# LED_driverV1_1.net
KiCad netlist of a schematic drawn in EAGLE
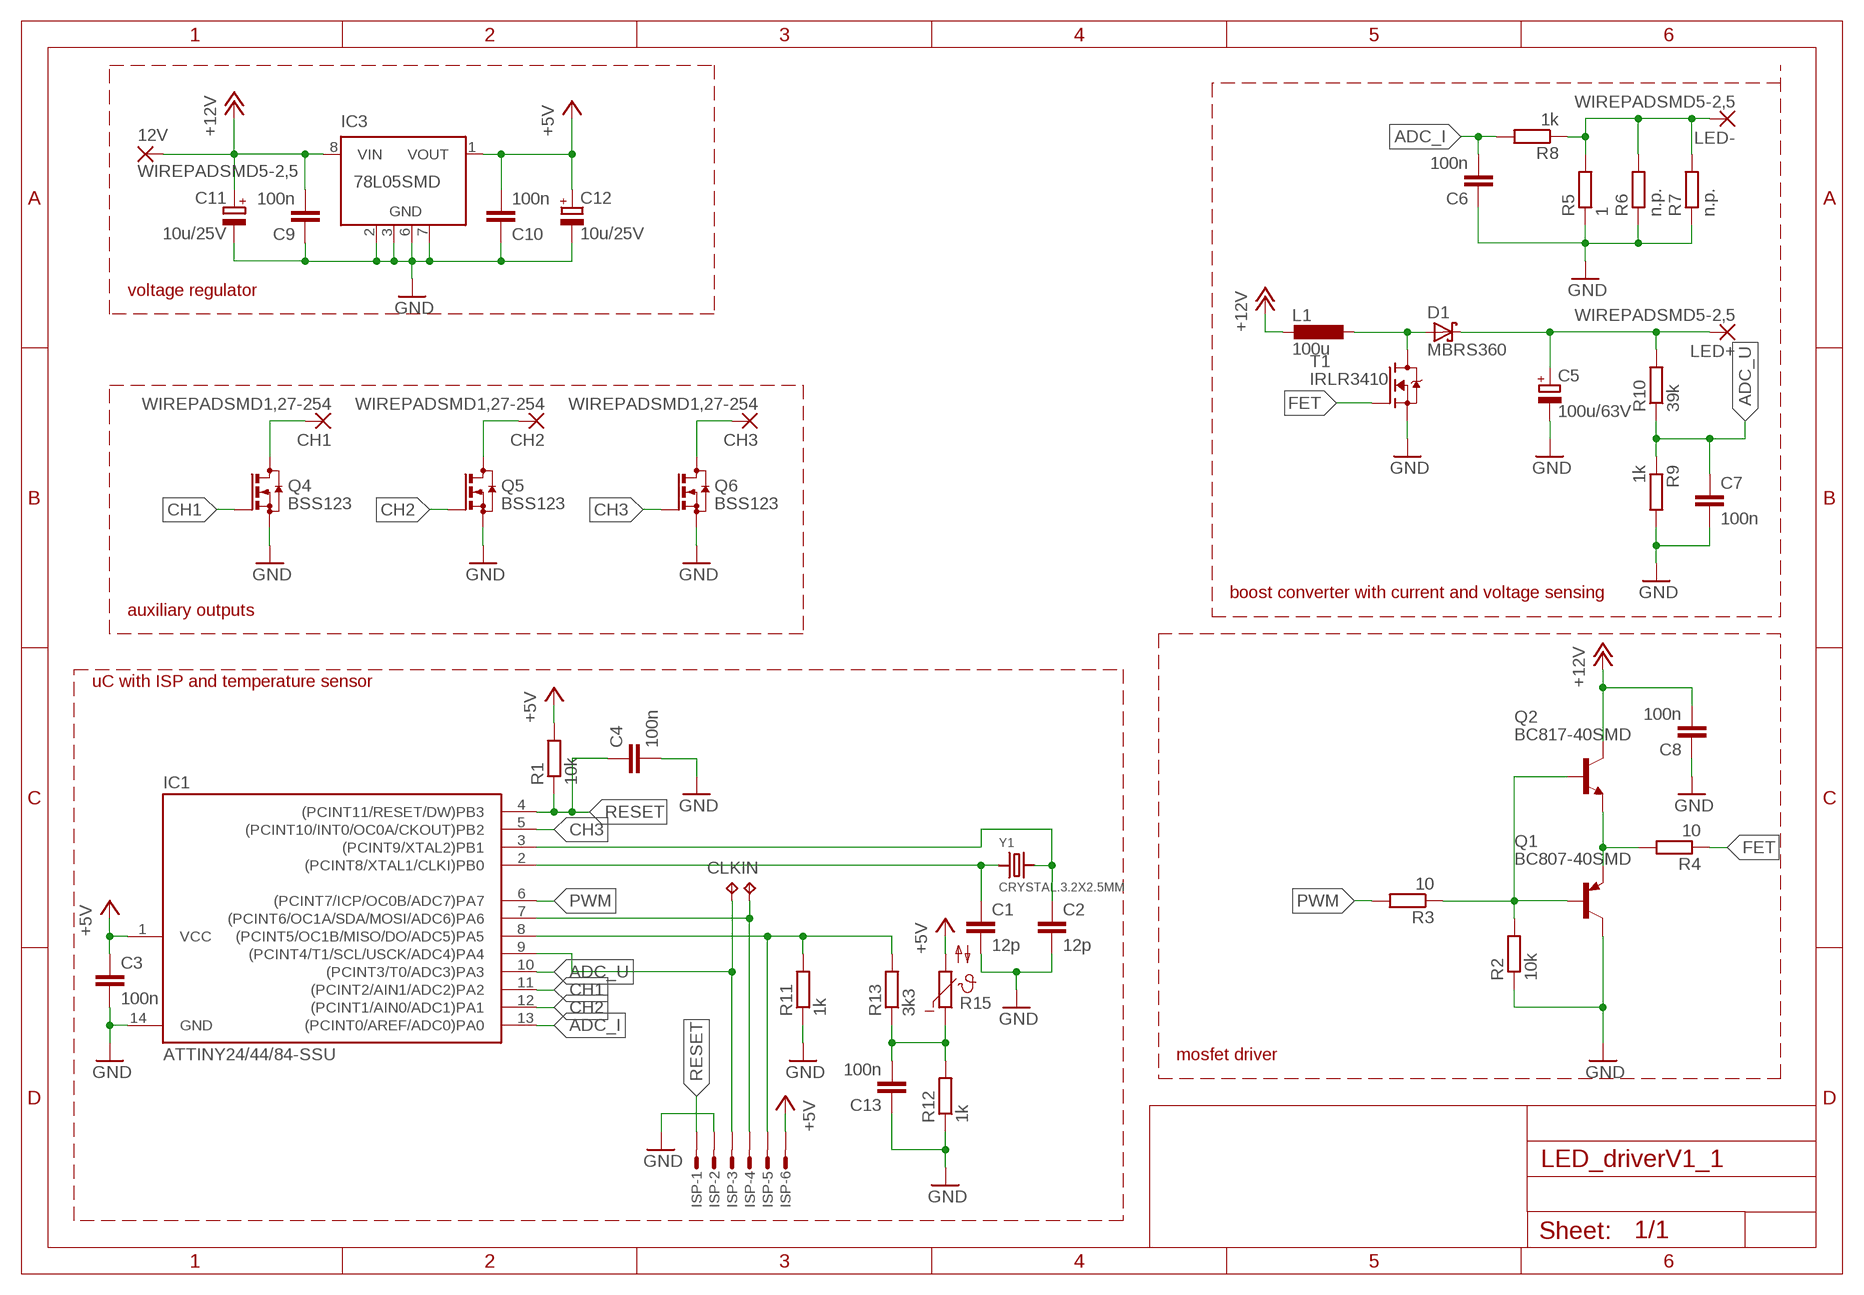
[diagram p0: schematic, sheet 1]

(export (version "E")
  (design (tool "Eeschema 10.0.6"))
  (components
    (comp (ref "12V")
      (value "WIREPADSMD5-2,5")
      (footprint "eagle-import:5-2,5")
      (libsource (lib "eagle-import") (part "WIREPADSMD5-2,5"))
    )
    (comp (ref "C1")
      (value "12p")
      (footprint "eagle-import:C0603K")
      (libsource (lib "eagle-import") (part "C-EUC0603K"))
    )
    (comp (ref "C2")
      (value "12p")
      (footprint "eagle-import:C0603K")
      (libsource (lib "eagle-import") (part "C-EUC0603K"))
    )
    (comp (ref "C3")
      (value "100n")
      (footprint "eagle-import:C0603K")
      (libsource (lib "eagle-import") (part "C-EUC0603K"))
    )
    (comp (ref "C4")
      (value "100n")
      (footprint "eagle-import:C0603K")
      (libsource (lib "eagle-import") (part "C-EUC0603K"))
    )
    (comp (ref "C5")
      (value "100u/63V")
      (footprint "eagle-import:153CLV-1010")
      (libsource (lib "eagle-import") (part "CPOL-EU153CLV-1010"))
    )
    (comp (ref "C6")
      (value "100n")
      (footprint "eagle-import:C0603K")
      (libsource (lib "eagle-import") (part "C-EUC0603K"))
    )
    (comp (ref "C7")
      (value "100n")
      (footprint "eagle-import:C0603K")
      (libsource (lib "eagle-import") (part "C-EUC0603K"))
    )
    (comp (ref "C8")
      (value "100n")
      (footprint "eagle-import:C0603K")
      (libsource (lib "eagle-import") (part "C-EUC0603K"))
    )
    (comp (ref "C9")
      (value "100n")
      (footprint "eagle-import:C0603K")
      (libsource (lib "eagle-import") (part "C-EUC0603K"))
    )
    (comp (ref "C10")
      (value "100n")
      (footprint "eagle-import:C0603K")
      (libsource (lib "eagle-import") (part "C-EUC0603K"))
    )
    (comp (ref "C11")
      (value "10u/25V")
      (footprint "eagle-import:153CLV-0405")
      (libsource (lib "eagle-import") (part "CPOL-EU153CLV-0405"))
    )
    (comp (ref "C12")
      (value "10u/25V")
      (footprint "eagle-import:153CLV-0405")
      (libsource (lib "eagle-import") (part "CPOL-EU153CLV-0405"))
    )
    (comp (ref "C13")
      (value "100n")
      (footprint "eagle-import:C0603K")
      (libsource (lib "eagle-import") (part "C-EUC0603K"))
    )
    (comp (ref "CH1")
      (value "WIREPADSMD1,27-254")
      (footprint "eagle-import:SMD1,27-2,54")
      (libsource (lib "eagle-import") (part "WIREPADSMD1,27-254"))
    )
    (comp (ref "CH2")
      (value "WIREPADSMD1,27-254")
      (footprint "eagle-import:SMD1,27-2,54")
      (libsource (lib "eagle-import") (part "WIREPADSMD1,27-254"))
    )
    (comp (ref "CH3")
      (value "WIREPADSMD1,27-254")
      (footprint "eagle-import:SMD1,27-2,54")
      (libsource (lib "eagle-import") (part "WIREPADSMD1,27-254"))
    )
    (comp (ref "CLK")
      (value "TPTP15R")
      (footprint "eagle-import:TP15R")
      (libsource (lib "eagle-import") (part "TPTP15R"))
    )
    (comp (ref "D1")
      (value "MBRS360")
      (footprint "eagle-import:SMC")
      (libsource (lib "eagle-import") (part "SCHOTTKY-DIODESMC"))
    )
    (comp (ref "IC1")
      (value "ATTINY24/44/84-SSU")
      (footprint "eagle-import:SOIC14")
      (libsource (lib "eagle-import") (part "ATTINY24/44/84-SSU"))
    )
    (comp (ref "IC3")
      (value "78L05SMD")
      (footprint "eagle-import:SO08")
      (libsource (lib "eagle-import") (part "78LSMD05"))
    )
    (comp (ref "IN")
      (value "TPTP15R")
      (footprint "eagle-import:TP15R")
      (libsource (lib "eagle-import") (part "TPTP15R"))
    )
    (comp (ref "ISP")
      (value "MICROMATCH-6SMF")
      (footprint "eagle-import:MMT-F-SMD-6")
      (libsource (lib "eagle-import") (part "MICROMATCH-6SMF"))
    )
    (comp (ref "L1")
      (value "100u")
      (footprint "eagle-import:PISM")
      (libsource (lib "eagle-import") (part "L-EUPISM"))
    )
    (comp (ref "LED+")
      (value "WIREPADSMD5-2,5")
      (footprint "eagle-import:5-2,5")
      (libsource (lib "eagle-import") (part "WIREPADSMD5-2,5"))
    )
    (comp (ref "LED-")
      (value "WIREPADSMD5-2,5")
      (footprint "eagle-import:5-2,5")
      (libsource (lib "eagle-import") (part "WIREPADSMD5-2,5"))
    )
    (comp (ref "Q1")
      (value "BC807-40SMD")
      (footprint "eagle-import:SOT23-BEC")
      (libsource (lib "eagle-import") (part "BC807SMD-40"))
    )
    (comp (ref "Q2")
      (value "BC817-40SMD")
      (footprint "eagle-import:SOT23-BEC")
      (libsource (lib "eagle-import") (part "BC817SMD-40"))
    )
    (comp (ref "Q4")
      (value "BSS123")
      (footprint "eagle-import:SOT23")
      (libsource (lib "eagle-import") (part "BSS123"))
    )
    (comp (ref "Q5")
      (value "BSS123")
      (footprint "eagle-import:SOT23")
      (libsource (lib "eagle-import") (part "BSS123"))
    )
    (comp (ref "Q6")
      (value "BSS123")
      (footprint "eagle-import:SOT23")
      (libsource (lib "eagle-import") (part "BSS123"))
    )
    (comp (ref "R1")
      (value "10k")
      (footprint "eagle-import:R0603")
      (libsource (lib "eagle-import") (part "R-EU_R0603"))
    )
    (comp (ref "R2")
      (value "10k")
      (footprint "eagle-import:R0603")
      (libsource (lib "eagle-import") (part "R-EU_R0603"))
    )
    (comp (ref "R3")
      (value "10")
      (footprint "eagle-import:R0603")
      (libsource (lib "eagle-import") (part "R-EU_R0603"))
    )
    (comp (ref "R4")
      (value "10")
      (footprint "eagle-import:R0603")
      (libsource (lib "eagle-import") (part "R-EU_R0603"))
    )
    (comp (ref "R5")
      (value "1")
      (footprint "eagle-import:R1206")
      (libsource (lib "eagle-import") (part "resistor_R-EU_R1206"))
    )
    (comp (ref "R6")
      (value "n.p.")
      (footprint "eagle-import:R1206")
      (libsource (lib "eagle-import") (part "resistor_R-EU_R1206"))
    )
    (comp (ref "R7")
      (value "n.p.")
      (footprint "eagle-import:R1206")
      (libsource (lib "eagle-import") (part "resistor_R-EU_R1206"))
    )
    (comp (ref "R8")
      (value "1k")
      (footprint "eagle-import:R0603")
      (libsource (lib "eagle-import") (part "R-EU_R0603"))
    )
    (comp (ref "R9")
      (value "1k")
      (footprint "eagle-import:R0603")
      (libsource (lib "eagle-import") (part "R-EU_R0603"))
    )
    (comp (ref "R10")
      (value "39k")
      (footprint "eagle-import:R0603")
      (libsource (lib "eagle-import") (part "R-EU_R0603"))
    )
    (comp (ref "R11")
      (value "1k")
      (footprint "eagle-import:R0603")
      (libsource (lib "eagle-import") (part "R-EU_R0603"))
    )
    (comp (ref "R12")
      (value "1k")
      (footprint "eagle-import:R0603")
      (libsource (lib "eagle-import") (part "R-EU_R0603"))
    )
    (comp (ref "R13")
      (value "3k3")
      (footprint "eagle-import:R0603")
      (libsource (lib "eagle-import") (part "R-EU_R0603"))
    )
    (comp (ref "R15")
      (value "NTC640")
      (footprint "eagle-import:P640")
      (libsource (lib "eagle-import") (part "NTC640"))
    )
    (comp (ref "T1")
      (value "IRLR3410")
      (footprint "eagle-import:TO252")
      (libsource (lib "eagle-import") (part "IRLR3410"))
    )
    (comp (ref "Y1")
      (value "CRYSTAL.3.2X2.5MM")
      (footprint "eagle-import:3.2X2.5MM")
      (libsource (lib "eagle-import") (part "CRYSTAL.3.2X2.5MM"))
    )
  )
  (nets
    (net (code "1") (name "+5V") (class "Default")
      (node (ref "C10") (pin "2") (pinfunction "2_2") (pintype "passive"))
      (node (ref "C12") (pin "+") (pinfunction "+_+") (pintype "passive"))
      (node (ref "C3") (pin "1") (pinfunction "1_1") (pintype "passive"))
      (node (ref "IC1") (pin "1") (pinfunction "VCC_1") (pintype "power_in"))
      (node (ref "IC3") (pin "1") (pinfunction "VOUT_1") (pintype "output"))
      (node (ref "ISP") (pin "6") (pinfunction "S_6") (pintype "passive"))
      (node (ref "R1") (pin "2") (pinfunction "2_2") (pintype "passive"))
      (node (ref "R15") (pin "2") (pinfunction "2_2") (pintype "passive"))
    )
    (net (code "2") (name "+12V") (class "Default")
      (node (ref "12V") (pin "1") (pinfunction "P_1") (pintype "passive"))
      (node (ref "C11") (pin "+") (pinfunction "+_+") (pintype "passive"))
      (node (ref "C8") (pin "2") (pinfunction "2_2") (pintype "passive"))
      (node (ref "C9") (pin "2") (pinfunction "2_2") (pintype "passive"))
      (node (ref "IC3") (pin "8") (pinfunction "VIN_8") (pintype "passive"))
      (node (ref "L1") (pin "2") (pinfunction "2_2") (pintype "passive"))
      (node (ref "Q2") (pin "C") (pinfunction "C_C") (pintype "passive"))
    )
    (net (code "3") (name "ADC_I") (class "Default")
      (node (ref "C6") (pin "2") (pinfunction "2_2") (pintype "passive"))
      (node (ref "IC1") (pin "13") (pinfunction "(PCINT0/AREF/ADC0)PA0_13") (pintype "bidirectional"))
      (node (ref "R8") (pin "2") (pinfunction "2_2") (pintype "passive"))
    )
    (net (code "4") (name "ADC_U") (class "Default")
      (node (ref "C7") (pin "1") (pinfunction "1_1") (pintype "passive"))
      (node (ref "IC1") (pin "10") (pinfunction "(PCINT3/T0/ADC3)PA3_10") (pintype "bidirectional"))
      (node (ref "R10") (pin "1") (pinfunction "1_1") (pintype "passive"))
      (node (ref "R9") (pin "1") (pinfunction "1_1") (pintype "passive"))
    )
    (net (code "5") (name "CH1") (class "Default")
      (node (ref "IC1") (pin "11") (pinfunction "(PCINT2/AIN1/ADC2)PA2_11") (pintype "bidirectional"))
      (node (ref "Q4") (pin "1") (pinfunction "G_1") (pintype "passive"))
    )
    (net (code "6") (name "CH2") (class "Default")
      (node (ref "IC1") (pin "12") (pinfunction "(PCINT1/AIN0/ADC1)PA1_12") (pintype "bidirectional"))
      (node (ref "Q5") (pin "1") (pinfunction "G_1") (pintype "passive"))
    )
    (net (code "7") (name "CH3") (class "Default")
      (node (ref "IC1") (pin "5") (pinfunction "(PCINT10/INT0/OC0A/CKOUT)PB2_5") (pintype "bidirectional"))
      (node (ref "Q6") (pin "1") (pinfunction "G_1") (pintype "passive"))
    )
    (net (code "8") (name "FET") (class "Default")
      (node (ref "R4") (pin "1") (pinfunction "1_1") (pintype "passive"))
      (node (ref "T1") (pin "1") (pinfunction "G_1") (pintype "passive"))
    )
    (net (code "9") (name "GND") (class "Default")
      (node (ref "C1") (pin "2") (pinfunction "2_2") (pintype "passive"))
      (node (ref "C10") (pin "1") (pinfunction "1_1") (pintype "passive"))
      (node (ref "C11") (pin "-") (pinfunction "-_-") (pintype "passive"))
      (node (ref "C12") (pin "-") (pinfunction "-_-") (pintype "passive"))
      (node (ref "C13") (pin "1") (pinfunction "1_1") (pintype "passive"))
      (node (ref "C2") (pin "2") (pinfunction "2_2") (pintype "passive"))
      (node (ref "C3") (pin "2") (pinfunction "2_2") (pintype "passive"))
      (node (ref "C4") (pin "2") (pinfunction "2_2") (pintype "passive"))
      (node (ref "C5") (pin "-") (pinfunction "-_-") (pintype "passive"))
      (node (ref "C6") (pin "1") (pinfunction "1_1") (pintype "passive"))
      (node (ref "C7") (pin "2") (pinfunction "2_2") (pintype "passive"))
      (node (ref "C8") (pin "1") (pinfunction "1_1") (pintype "passive"))
      (node (ref "C9") (pin "1") (pinfunction "1_1") (pintype "passive"))
      (node (ref "IC1") (pin "14") (pinfunction "GND_14") (pintype "power_in"))
      (node (ref "IC3") (pin "2") (pinfunction "GND_2") (pintype "power_in"))
      (node (ref "IC3") (pin "3") (pinfunction "GND_3") (pintype "power_in"))
      (node (ref "IC3") (pin "6") (pinfunction "GND_6") (pintype "power_in"))
      (node (ref "IC3") (pin "7") (pinfunction "GND_7") (pintype "power_in"))
      (node (ref "ISP") (pin "2") (pinfunction "S_2") (pintype "passive"))
      (node (ref "Q1") (pin "C") (pinfunction "C_C") (pintype "passive"))
      (node (ref "Q4") (pin "2") (pinfunction "S_2") (pintype "passive"))
      (node (ref "Q5") (pin "2") (pinfunction "S_2") (pintype "passive"))
      (node (ref "Q6") (pin "2") (pinfunction "S_2") (pintype "passive"))
      (node (ref "R11") (pin "1") (pinfunction "1_1") (pintype "passive"))
      (node (ref "R12") (pin "1") (pinfunction "1_1") (pintype "passive"))
      (node (ref "R2") (pin "1") (pinfunction "1_1") (pintype "passive"))
      (node (ref "R5") (pin "1") (pinfunction "1_1") (pintype "passive"))
      (node (ref "R6") (pin "1") (pinfunction "1_1") (pintype "passive"))
      (node (ref "R7") (pin "1") (pinfunction "1_1") (pintype "passive"))
      (node (ref "R9") (pin "2") (pinfunction "2_2") (pintype "passive"))
      (node (ref "T1") (pin "2") (pinfunction "S_2") (pintype "passive"))
    )
    (net (code "10") (name "Net-(C13-Pad2)") (class "Default")
      (node (ref "C13") (pin "2") (pinfunction "2_2") (pintype "passive"))
      (node (ref "R12") (pin "2") (pinfunction "2_2") (pintype "passive"))
      (node (ref "R13") (pin "1") (pinfunction "1_1") (pintype "passive"))
      (node (ref "R15") (pin "1") (pinfunction "1_1") (pintype "passive"))
    )
    (net (code "11") (name "Net-(CH1-P)") (class "Default")
      (node (ref "CH1") (pin "1") (pinfunction "P_1") (pintype "passive"))
      (node (ref "Q4") (pin "3") (pinfunction "D_3") (pintype "passive"))
    )
    (net (code "12") (name "Net-(CH2-P)") (class "Default")
      (node (ref "CH2") (pin "1") (pinfunction "P_1") (pintype "passive"))
      (node (ref "Q5") (pin "3") (pinfunction "D_3") (pintype "passive"))
    )
    (net (code "13") (name "Net-(CH3-P)") (class "Default")
      (node (ref "CH3") (pin "1") (pinfunction "P_1") (pintype "passive"))
      (node (ref "Q6") (pin "3") (pinfunction "D_3") (pintype "passive"))
    )
    (net (code "14") (name "Net-(IC1-(PCINT4{slash}T1{slash}SCL{slash}USCK{slash}ADC4)PA4)") (class "Default")
      (node (ref "CLK") (pin "TP") (pinfunction "TP_TP") (pintype "input"))
      (node (ref "IC1") (pin "9") (pinfunction "(PCINT4/T1/SCL/USCK/ADC4)PA4_9") (pintype "bidirectional"))
      (node (ref "ISP") (pin "3") (pinfunction "S_3") (pintype "passive"))
    )
    (net (code "15") (name "Net-(IC1-(PCINT5{slash}OC1B{slash}MISO{slash}DO{slash}ADC5)PA5)") (class "Default")
      (node (ref "IC1") (pin "8") (pinfunction "(PCINT5/OC1B/MISO/DO/ADC5)PA5_8") (pintype "bidirectional"))
      (node (ref "ISP") (pin "5") (pinfunction "S_5") (pintype "passive"))
      (node (ref "R11") (pin "2") (pinfunction "2_2") (pintype "passive"))
      (node (ref "R13") (pin "2") (pinfunction "2_2") (pintype "passive"))
    )
    (net (code "16") (name "Net-(IC1-(PCINT6{slash}OC1A{slash}SDA{slash}MOSI{slash}ADC6)PA6)") (class "Default")
      (node (ref "IC1") (pin "7") (pinfunction "(PCINT6/OC1A/SDA/MOSI/ADC6)PA6_7") (pintype "bidirectional"))
      (node (ref "IN") (pin "TP") (pinfunction "TP_TP") (pintype "input"))
      (node (ref "ISP") (pin "4") (pinfunction "S_4") (pintype "passive"))
    )
    (net (code "17") (name "Net-(IC1-(PCINT8{slash}XTAL1{slash}CLKI)PB0)") (class "Default")
      (node (ref "C1") (pin "1") (pinfunction "1_1") (pintype "passive"))
      (node (ref "IC1") (pin "2") (pinfunction "(PCINT8/XTAL1/CLKI)PB0_2") (pintype "bidirectional"))
      (node (ref "Y1") (pin "1") (pinfunction "1_1") (pintype "passive"))
    )
    (net (code "18") (name "Net-(IC1-(PCINT9{slash}XTAL2)PB1)") (class "Default")
      (node (ref "C2") (pin "1") (pinfunction "1_1") (pintype "passive"))
      (node (ref "IC1") (pin "3") (pinfunction "(PCINT9/XTAL2)PB1_3") (pintype "bidirectional"))
      (node (ref "Y1") (pin "3") (pinfunction "2_3") (pintype "passive"))
    )
    (net (code "19") (name "Net-(LED+-P)") (class "Default")
      (node (ref "C5") (pin "+") (pinfunction "+_+") (pintype "passive"))
      (node (ref "D1") (pin "C") (pinfunction "C_C") (pintype "passive"))
      (node (ref "LED+") (pin "1") (pinfunction "P_1") (pintype "passive"))
      (node (ref "R10") (pin "2") (pinfunction "2_2") (pintype "passive"))
    )
    (net (code "20") (name "Net-(LED--P)") (class "Default")
      (node (ref "LED-") (pin "1") (pinfunction "P_1") (pintype "passive"))
      (node (ref "R5") (pin "2") (pinfunction "2_2") (pintype "passive"))
      (node (ref "R6") (pin "2") (pinfunction "2_2") (pintype "passive"))
      (node (ref "R7") (pin "2") (pinfunction "2_2") (pintype "passive"))
      (node (ref "R8") (pin "1") (pinfunction "1_1") (pintype "passive"))
    )
    (net (code "21") (name "Net-(Q1-PadB)") (class "Default")
      (node (ref "Q1") (pin "B") (pinfunction "B_B") (pintype "passive"))
      (node (ref "Q2") (pin "B") (pinfunction "B_B") (pintype "passive"))
      (node (ref "R2") (pin "2") (pinfunction "2_2") (pintype "passive"))
      (node (ref "R3") (pin "1") (pinfunction "1_1") (pintype "passive"))
    )
    (net (code "22") (name "Net-(Q1-PadE)") (class "Default")
      (node (ref "Q1") (pin "E") (pinfunction "E_E") (pintype "passive"))
      (node (ref "Q2") (pin "E") (pinfunction "E_E") (pintype "passive"))
      (node (ref "R4") (pin "2") (pinfunction "2_2") (pintype "passive"))
    )
    (net (code "23") (name "Net-(T1-D)") (class "Default")
      (node (ref "D1") (pin "A") (pinfunction "A_A") (pintype "passive"))
      (node (ref "L1") (pin "1") (pinfunction "1_1") (pintype "passive"))
      (node (ref "T1") (pin "3") (pinfunction "D_3") (pintype "passive"))
    )
    (net (code "24") (name "PWM") (class "Default")
      (node (ref "IC1") (pin "6") (pinfunction "(PCINT7/ICP/OC0B/ADC7)PA7_6") (pintype "bidirectional"))
      (node (ref "R3") (pin "2") (pinfunction "2_2") (pintype "passive"))
    )
    (net (code "25") (name "RESET") (class "Default")
      (node (ref "C4") (pin "1") (pinfunction "1_1") (pintype "passive"))
      (node (ref "IC1") (pin "4") (pinfunction "(PCINT11/RESET/DW)PB3_4") (pintype "bidirectional"))
      (node (ref "ISP") (pin "1") (pinfunction "S_1") (pintype "passive"))
      (node (ref "R1") (pin "1") (pinfunction "1_1") (pintype "passive"))
    )
  )
)
